# SqTeclado.net
KiCad netlist of a schematic drawn in Altium Designer
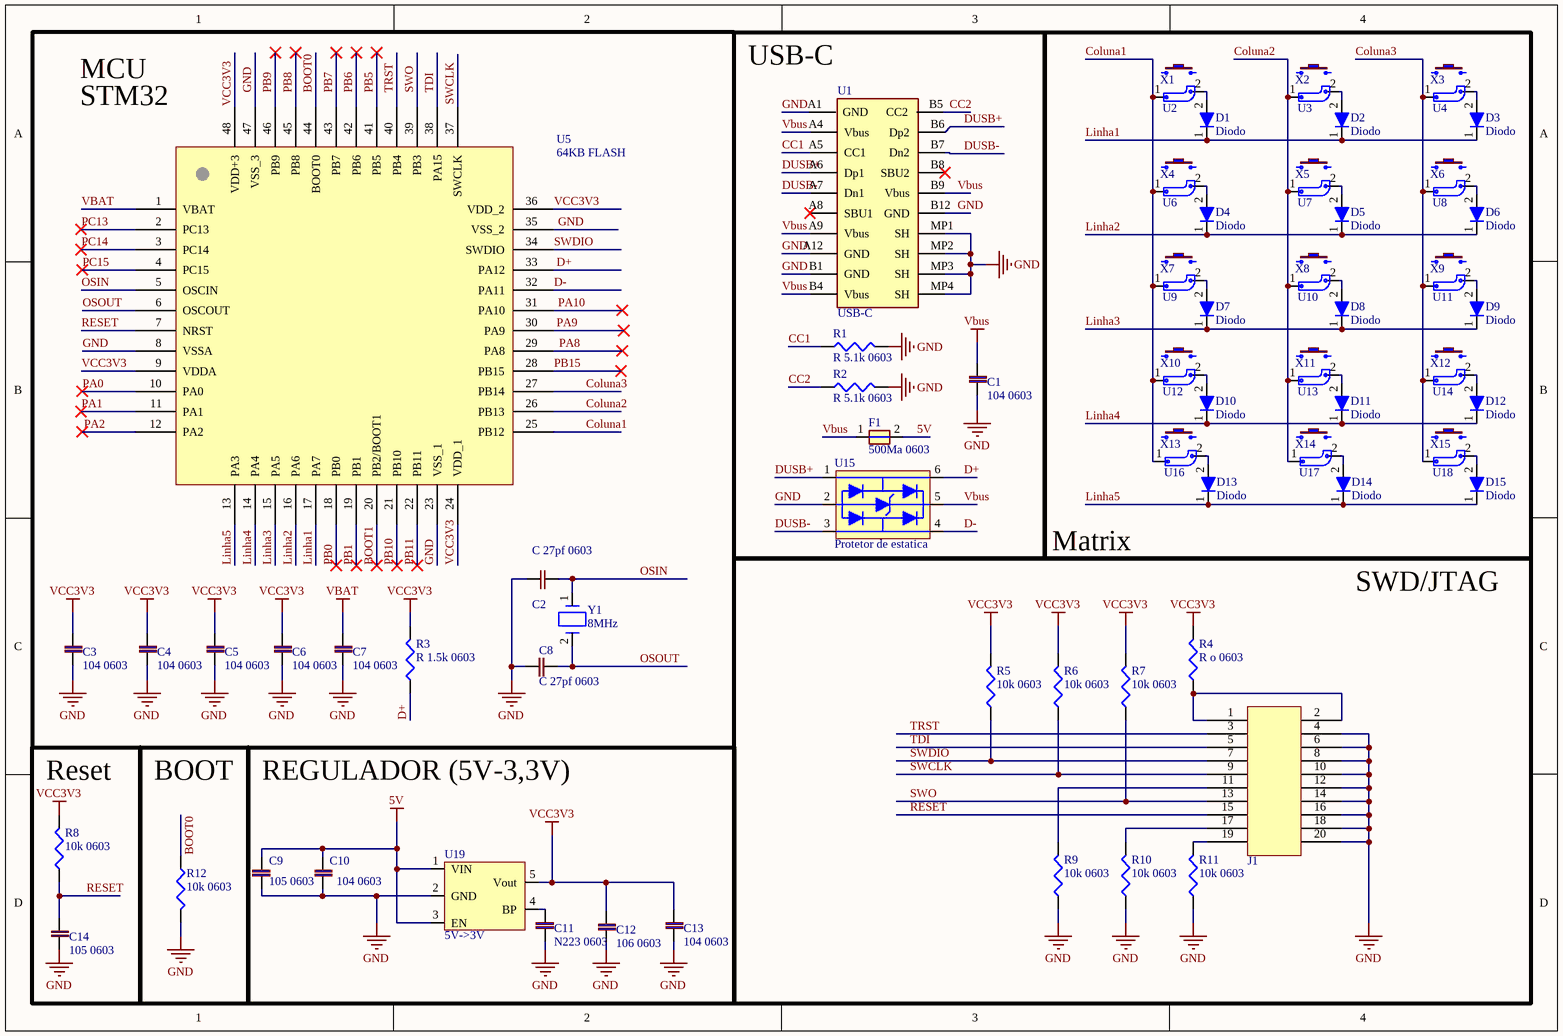
[diagram p0: SqTeclado.SchDoc]

(export (version "E")
  (design (tool "Eeschema 10.0.6"))
  (components
    (comp (ref "C1")
      (value "104 0603")
      (footprint "Cap 104 0603")
      (description "16V 100nF X7R ±10% 0603 Multilayer Ceramic Capacitors MLCC - SMD/SMT ROHS")
      (fields
        (field (name "MANUFACTURER") "Yageo Group")
        (field (name "MANUFACTURER PART NUMBER") "CC0603KRX7R7BB104")
      )
      (libsource (lib "Esqlib") (part "CC0603KRX7R7BB104"))
    )
    (comp (ref "C2")
      (value "C 27pf 0603")
      (footprint "c 27pf 0603")
      (description "0603 27 pF 50 V ±1 % Tolerance NP0 SMT Multilayer Ceramic Capacitor")
      (fields
        (field (name "MANUFACTURER") "Yageo Group")
        (field (name "MANUFACTURER PART NUMBER") "CC0603FRNPO9BN270")
      )
      (libsource (lib "Esqlib") (part "CC0603FRNPO9BN270"))
    )
    (comp (ref "C3")
      (value "104 0603")
      (footprint "Cap 104 0603")
      (description "16V 100nF X7R ±10% 0603 Multilayer Ceramic Capacitors MLCC - SMD/SMT ROHS")
      (fields
        (field (name "MANUFACTURER") "Yageo Group")
        (field (name "MANUFACTURER PART NUMBER") "CC0603KRX7R7BB104")
      )
      (libsource (lib "Esqlib") (part "CC0603KRX7R7BB104"))
    )
    (comp (ref "C4")
      (value "104 0603")
      (footprint "Cap 104 0603")
      (description "16V 100nF X7R ±10% 0603 Multilayer Ceramic Capacitors MLCC - SMD/SMT ROHS")
      (fields
        (field (name "MANUFACTURER") "Yageo Group")
        (field (name "MANUFACTURER PART NUMBER") "CC0603KRX7R7BB104")
      )
      (libsource (lib "Esqlib") (part "CC0603KRX7R7BB104"))
    )
    (comp (ref "C5")
      (value "104 0603")
      (footprint "Cap 104 0603")
      (description "16V 100nF X7R ±10% 0603 Multilayer Ceramic Capacitors MLCC - SMD/SMT ROHS")
      (fields
        (field (name "MANUFACTURER") "Yageo Group")
        (field (name "MANUFACTURER PART NUMBER") "CC0603KRX7R7BB104")
      )
      (libsource (lib "Esqlib") (part "CC0603KRX7R7BB104"))
    )
    (comp (ref "C6")
      (value "104 0603")
      (footprint "Cap 104 0603")
      (description "16V 100nF X7R ±10% 0603 Multilayer Ceramic Capacitors MLCC - SMD/SMT ROHS")
      (fields
        (field (name "MANUFACTURER") "Yageo Group")
        (field (name "MANUFACTURER PART NUMBER") "CC0603KRX7R7BB104")
      )
      (libsource (lib "Esqlib") (part "CC0603KRX7R7BB104"))
    )
    (comp (ref "C7")
      (value "104 0603")
      (footprint "Cap 104 0603")
      (description "16V 100nF X7R ±10% 0603 Multilayer Ceramic Capacitors MLCC - SMD/SMT ROHS")
      (fields
        (field (name "MANUFACTURER") "Yageo Group")
        (field (name "MANUFACTURER PART NUMBER") "CC0603KRX7R7BB104")
      )
      (libsource (lib "Esqlib") (part "CC0603KRX7R7BB104"))
    )
    (comp (ref "C8")
      (value "C 27pf 0603")
      (footprint "c 27pf 0603")
      (description "0603 27 pF 50 V ±1 % Tolerance NP0 SMT Multilayer Ceramic Capacitor")
      (fields
        (field (name "MANUFACTURER") "Yageo Group")
        (field (name "MANUFACTURER PART NUMBER") "CC0603FRNPO9BN270")
      )
      (libsource (lib "Esqlib") (part "CC0603FRNPO9BN270"))
    )
    (comp (ref "C9")
      (value "105 0603")
      (footprint "cap 105 0603")
      (description "10V 1uF X7R ±10% 0603 Multilayer Ceramic Capacitors MLCC - SMD/SMT ROHS")
      (fields
        (field (name "MANUFACTURER") "Samsung Electro-Mechanics")
        (field (name "MANUFACTURER PART NUMBER") "CL10B105KP8NNNC")
      )
      (libsource (lib "") (part "CL10B105KP8NNNC_1"))
    )
    (comp (ref "C10")
      (value "104 0603")
      (footprint "Cap 104 0603")
      (description "16V 100nF X7R ±10% 0603 Multilayer Ceramic Capacitors MLCC - SMD/SMT ROHS")
      (fields
        (field (name "MANUFACTURER") "Yageo Group")
        (field (name "MANUFACTURER PART NUMBER") "CC0603KRX7R7BB104")
      )
      (libsource (lib "Esqlib") (part "CC0603KRX7R7BB104"))
    )
    (comp (ref "C11")
      (value "N223 0603")
      (footprint "cap 223 0603")
      (fields
        (field (name "MANUFACTURER") "Samsung Electro-Mechanics")
        (field (name "MANUFACTURER PART NUMBER") "CL10B223KB8WPNC")
        (field (name "TOLERANCE") "10%")
      )
      (libsource (lib "Esqlib") (part "CL10B223KB8WPNC"))
    )
    (comp (ref "C12")
      (value "106 0603")
      (footprint "cap 106 0603")
      (description "Multilayer Ceramic Capacitors (High dielectric type), 10V, 10 uF, ± 20 %, 0603, X5R, RoHS")
      (fields
        (field (name "MANUFACTURER") "Taiyo Yuden")
        (field (name "MANUFACTURER PART NUMBER") "LMK107BBJ106MALT")
      )
      (libsource (lib "Esqlib") (part "LMK107BBJ106MALT"))
    )
    (comp (ref "C13")
      (value "104 0603")
      (footprint "Cap 104 0603")
      (description "16V 100nF X7R ±10% 0603 Multilayer Ceramic Capacitors MLCC - SMD/SMT ROHS")
      (fields
        (field (name "MANUFACTURER") "Yageo Group")
        (field (name "MANUFACTURER PART NUMBER") "CC0603KRX7R7BB104")
      )
      (libsource (lib "Esqlib") (part "CC0603KRX7R7BB104"))
    )
    (comp (ref "C14")
      (value "105 0603")
      (footprint "cap 105 0603")
      (description "10V 1uF X7R ±10% 0603 Multilayer Ceramic Capacitors MLCC - SMD/SMT ROHS")
      (fields
        (field (name "MANUFACTURER") "Samsung Electro-Mechanics")
        (field (name "MANUFACTURER PART NUMBER") "CL10B105KP8NNNC")
      )
      (libsource (lib "Esqlib") (part "CL10B105KP8NNNC"))
    )
    (comp (ref "D1")
      (value "Diodo")
      (footprint "Diodo C")
      (description "Rectifier Diode Schottky 40V 0.03A 2-Pin SOD-323 T/R / DIODE SCHOTTKY 30V 30MA SOD323")
      (fields (field (name "MANUFACTURER") "onsemi") (field (name "MANUFACTURER PART NUMBER") "RB751V40T1G"))
      (libsource (lib "Esqlib") (part "RB751V40T1G"))
    )
    (comp (ref "D2")
      (value "Diodo")
      (footprint "Diodo C")
      (description "Rectifier Diode Schottky 40V 0.03A 2-Pin SOD-323 T/R / DIODE SCHOTTKY 30V 30MA SOD323")
      (fields (field (name "MANUFACTURER") "onsemi") (field (name "MANUFACTURER PART NUMBER") "RB751V40T1G"))
      (libsource (lib "Esqlib") (part "RB751V40T1G"))
    )
    (comp (ref "D3")
      (value "Diodo")
      (footprint "Diodo C")
      (description "Rectifier Diode Schottky 40V 0.03A 2-Pin SOD-323 T/R / DIODE SCHOTTKY 30V 30MA SOD323")
      (fields (field (name "MANUFACTURER") "onsemi") (field (name "MANUFACTURER PART NUMBER") "RB751V40T1G"))
      (libsource (lib "Esqlib") (part "RB751V40T1G"))
    )
    (comp (ref "D4")
      (value "Diodo")
      (footprint "Diodo C")
      (description "Rectifier Diode Schottky 40V 0.03A 2-Pin SOD-323 T/R / DIODE SCHOTTKY 30V 30MA SOD323")
      (fields (field (name "MANUFACTURER") "onsemi") (field (name "MANUFACTURER PART NUMBER") "RB751V40T1G"))
      (libsource (lib "Esqlib") (part "RB751V40T1G"))
    )
    (comp (ref "D5")
      (value "Diodo")
      (footprint "Diodo C")
      (description "Rectifier Diode Schottky 40V 0.03A 2-Pin SOD-323 T/R / DIODE SCHOTTKY 30V 30MA SOD323")
      (fields (field (name "MANUFACTURER") "onsemi") (field (name "MANUFACTURER PART NUMBER") "RB751V40T1G"))
      (libsource (lib "Esqlib") (part "RB751V40T1G"))
    )
    (comp (ref "D6")
      (value "Diodo")
      (footprint "Diodo C")
      (description "Rectifier Diode Schottky 40V 0.03A 2-Pin SOD-323 T/R / DIODE SCHOTTKY 30V 30MA SOD323")
      (fields (field (name "MANUFACTURER") "onsemi") (field (name "MANUFACTURER PART NUMBER") "RB751V40T1G"))
      (libsource (lib "Esqlib") (part "RB751V40T1G"))
    )
    (comp (ref "D7")
      (value "Diodo")
      (footprint "Diodo C")
      (description "Rectifier Diode Schottky 40V 0.03A 2-Pin SOD-323 T/R / DIODE SCHOTTKY 30V 30MA SOD323")
      (fields (field (name "MANUFACTURER") "onsemi") (field (name "MANUFACTURER PART NUMBER") "RB751V40T1G"))
      (libsource (lib "Esqlib") (part "RB751V40T1G"))
    )
    (comp (ref "D8")
      (value "Diodo")
      (footprint "Diodo C")
      (description "Rectifier Diode Schottky 40V 0.03A 2-Pin SOD-323 T/R / DIODE SCHOTTKY 30V 30MA SOD323")
      (fields (field (name "MANUFACTURER") "onsemi") (field (name "MANUFACTURER PART NUMBER") "RB751V40T1G"))
      (libsource (lib "Esqlib") (part "RB751V40T1G"))
    )
    (comp (ref "D9")
      (value "Diodo")
      (footprint "Diodo C")
      (description "Rectifier Diode Schottky 40V 0.03A 2-Pin SOD-323 T/R / DIODE SCHOTTKY 30V 30MA SOD323")
      (fields (field (name "MANUFACTURER") "onsemi") (field (name "MANUFACTURER PART NUMBER") "RB751V40T1G"))
      (libsource (lib "Esqlib") (part "RB751V40T1G"))
    )
    (comp (ref "D10")
      (value "Diodo")
      (footprint "Diodo C")
      (description "Rectifier Diode Schottky 40V 0.03A 2-Pin SOD-323 T/R / DIODE SCHOTTKY 30V 30MA SOD323")
      (fields (field (name "MANUFACTURER") "onsemi") (field (name "MANUFACTURER PART NUMBER") "RB751V40T1G"))
      (libsource (lib "Esqlib") (part "RB751V40T1G"))
    )
    (comp (ref "D11")
      (value "Diodo")
      (footprint "Diodo C")
      (description "Rectifier Diode Schottky 40V 0.03A 2-Pin SOD-323 T/R / DIODE SCHOTTKY 30V 30MA SOD323")
      (fields (field (name "MANUFACTURER") "onsemi") (field (name "MANUFACTURER PART NUMBER") "RB751V40T1G"))
      (libsource (lib "Esqlib") (part "RB751V40T1G"))
    )
    (comp (ref "D12")
      (value "Diodo")
      (footprint "Diodo C")
      (description "Rectifier Diode Schottky 40V 0.03A 2-Pin SOD-323 T/R / DIODE SCHOTTKY 30V 30MA SOD323")
      (fields (field (name "MANUFACTURER") "onsemi") (field (name "MANUFACTURER PART NUMBER") "RB751V40T1G"))
      (libsource (lib "Esqlib") (part "RB751V40T1G"))
    )
    (comp (ref "D13")
      (value "Diodo")
      (footprint "Diodo C")
      (description "Rectifier Diode Schottky 40V 0.03A 2-Pin SOD-323 T/R / DIODE SCHOTTKY 30V 30MA SOD323")
      (fields (field (name "MANUFACTURER") "onsemi") (field (name "MANUFACTURER PART NUMBER") "RB751V40T1G"))
      (libsource (lib "Esqlib") (part "RB751V40T1G"))
    )
    (comp (ref "D14")
      (value "Diodo")
      (footprint "Diodo C")
      (description "Rectifier Diode Schottky 40V 0.03A 2-Pin SOD-323 T/R / DIODE SCHOTTKY 30V 30MA SOD323")
      (fields (field (name "MANUFACTURER") "onsemi") (field (name "MANUFACTURER PART NUMBER") "RB751V40T1G"))
      (libsource (lib "Esqlib") (part "RB751V40T1G"))
    )
    (comp (ref "D15")
      (value "Diodo")
      (footprint "Diodo C")
      (description "Rectifier Diode Schottky 40V 0.03A 2-Pin SOD-323 T/R / DIODE SCHOTTKY 30V 30MA SOD323")
      (fields (field (name "MANUFACTURER") "onsemi") (field (name "MANUFACTURER PART NUMBER") "RB751V40T1G"))
      (libsource (lib "Esqlib") (part "RB751V40T1G"))
    )
    (comp (ref "F1")
      (value "500Ma 0603")
      (footprint "F 500ma 0603")
      (description "Fuse Chip Fast Acting 0.5A 32V SMD Solder Pad 0603 1.6 X 0.8 X 0.54mm T/R UL/cUL")
      (fields
        (field (name "MANUFACTURER") "Panasonic")
        (field (name "MANUFACTURER PART NUMBER") "ERB-RE0R50V")
      )
      (libsource (lib "Esqlib") (part "ERB-RE0R50V"))
    )
    (comp (ref "J1")
      (value "70247-2051")
      (footprint "Conector 20 pinos angulado p/ programação")
      (description "Conn Shrouded Header (4 Sides) HDR 20 POS 2.54mm Solder RA Side Entry Thru-HoleC-Grid Tray")
      (fields (field (name "MANUFACTURER") "Molex"))
      (libsource (lib "Esqlib") (part "70247-2051"))
    )
    (comp (ref "R1")
      (value "R 5.1k 0603")
      (footprint "R 5.1k 0603")
      (description "Res Thick Film 0603 5.1K Ohm 1% 0.1W(1/10W) ±100ppm/C Pad SMD T/R")
      (fields
        (field (name "MANUFACTURER") "Yageo Group")
        (field (name "MANUFACTURER PART NUMBER") "RC0603FR-075K1L")
      )
      (libsource (lib "Esqlib") (part "RC0603FR-075K1L"))
    )
    (comp (ref "R2")
      (value "R 5.1k 0603")
      (footprint "R 5.1k 0603")
      (description "Res Thick Film 0603 5.1K Ohm 1% 0.1W(1/10W) ±100ppm/C Pad SMD T/R")
      (fields
        (field (name "MANUFACTURER") "Yageo Group")
        (field (name "MANUFACTURER PART NUMBER") "RC0603FR-075K1L")
      )
      (libsource (lib "Esqlib") (part "RC0603FR-075K1L"))
    )
    (comp (ref "R3")
      (value "R 1.5k 0603")
      (footprint "R 1.5k 0603")
      (description "100Mw Thick Film Resistors 100Ppm/ 5% 1.5K 0603 Chip Resistor Surface Mount Rohs")
      (fields
        (field (name "MANUFACTURER") "Yageo Group")
        (field (name "MANUFACTURER PART NUMBER") "RC0603JR-071K5L")
      )
      (libsource (lib "Esqlib") (part "RC0603JR-071K5L"))
    )
    (comp (ref "R4")
      (value "R o 0603")
      (footprint "R 0 0603")
      (description "GENERAL PURPOSE CHIP RESISTOR Metal Glaze/thick Film, 0.1W, 0ohm, Surface Mount, 0603")
      (fields
        (field (name "MANUFACTURER") "Yageo Group")
        (field (name "MANUFACTURER PART NUMBER") "RC0603JR-070RL")
      )
      (libsource (lib "Esqlib") (part "RC0603JR-070RL"))
    )
    (comp (ref "R5")
      (value "10k 0603")
      (footprint "Resistor 10k 0603")
      (description "100mW Thick Film Resistors ±1% ±100ppm/℃ 10kΩ 0603 Chip Resistor - Surface Mount ROHS")
      (fields
        (field (name "MANUFACTURER") "Vishay")
        (field (name "MANUFACTURER PART NUMBER") "CRCW060310K0FKEA")
      )
      (libsource (lib "Esqlib") (part "CRCW060310K0FKEA"))
    )
    (comp (ref "R6")
      (value "10k 0603")
      (footprint "Resistor 10k 0603")
      (description "100mW Thick Film Resistors ±1% ±100ppm/℃ 10kΩ 0603 Chip Resistor - Surface Mount ROHS")
      (fields
        (field (name "MANUFACTURER") "Vishay")
        (field (name "MANUFACTURER PART NUMBER") "CRCW060310K0FKEA")
      )
      (libsource (lib "Esqlib") (part "CRCW060310K0FKEA"))
    )
    (comp (ref "R7")
      (value "10k 0603")
      (footprint "Resistor 10k 0603")
      (description "100mW Thick Film Resistors ±1% ±100ppm/℃ 10kΩ 0603 Chip Resistor - Surface Mount ROHS")
      (fields
        (field (name "MANUFACTURER") "Vishay")
        (field (name "MANUFACTURER PART NUMBER") "CRCW060310K0FKEA")
      )
      (libsource (lib "Esqlib") (part "CRCW060310K0FKEA"))
    )
    (comp (ref "R8")
      (value "10k 0603")
      (footprint "Resistor 10k 0603")
      (description "100mW Thick Film Resistors ±1% ±100ppm/℃ 10kΩ 0603 Chip Resistor - Surface Mount ROHS")
      (fields
        (field (name "MANUFACTURER") "Vishay")
        (field (name "MANUFACTURER PART NUMBER") "CRCW060310K0FKEA")
      )
      (libsource (lib "Esqlib") (part "CRCW060310K0FKEA"))
    )
    (comp (ref "R9")
      (value "10k 0603")
      (footprint "Resistor 10k 0603")
      (description "100mW Thick Film Resistors ±1% ±100ppm/℃ 10kΩ 0603 Chip Resistor - Surface Mount ROHS")
      (fields
        (field (name "MANUFACTURER") "Vishay")
        (field (name "MANUFACTURER PART NUMBER") "CRCW060310K0FKEA")
      )
      (libsource (lib "Esqlib") (part "CRCW060310K0FKEA"))
    )
    (comp (ref "R10")
      (value "10k 0603")
      (footprint "Resistor 10k 0603")
      (description "100mW Thick Film Resistors ±1% ±100ppm/℃ 10kΩ 0603 Chip Resistor - Surface Mount ROHS")
      (fields
        (field (name "MANUFACTURER") "Vishay")
        (field (name "MANUFACTURER PART NUMBER") "CRCW060310K0FKEA")
      )
      (libsource (lib "Esqlib") (part "CRCW060310K0FKEA"))
    )
    (comp (ref "R11")
      (value "10k 0603")
      (footprint "Resistor 10k 0603")
      (description "100mW Thick Film Resistors ±1% ±100ppm/℃ 10kΩ 0603 Chip Resistor - Surface Mount ROHS")
      (fields
        (field (name "MANUFACTURER") "Vishay")
        (field (name "MANUFACTURER PART NUMBER") "CRCW060310K0FKEA")
      )
      (libsource (lib "Esqlib") (part "CRCW060310K0FKEA"))
    )
    (comp (ref "R12")
      (value "10k 0603")
      (footprint "Resistor 10k 0603")
      (description "100mW Thick Film Resistors ±1% ±100ppm/℃ 10kΩ 0603 Chip Resistor - Surface Mount ROHS")
      (fields
        (field (name "MANUFACTURER") "Vishay")
        (field (name "MANUFACTURER PART NUMBER") "CRCW060310K0FKEA")
      )
      (libsource (lib "Esqlib") (part "CRCW060310K0FKEA"))
    )
    (comp (ref "U1")
      (value "USB-C")
      (footprint "USB-C")
      (description "USB Connector, 16 Contact(s), Male, Right Angle, Surface Mount Terminal, Locking, Receptacle")
      (fields
        (field (name "MANUFACTURER") "Global Connector Technology")
        (field (name "MANUFACTURER PART NUMBER") "USB4110-GF-A")
      )
      (libsource (lib "Esqlib") (part "USB4110-GF-A"))
    )
    (comp (ref "U2")
      (value "suporte hot-swap")
      (footprint "Suporte Hot-Swap")
      (description "Kailh Switch Sockets For Mx-Compatible Mechanical Keys - 20 Pack ¦Adafruit 4958")
      (fields
        (field (name "MANUFACTURER") "Adafruit Industries")
        (field (name "MANUFACTURER PART NUMBER") "4958")
      )
      (libsource (lib "Esqlib") (part "4958"))
    )
    (comp (ref "U3")
      (value "suporte hot-swap")
      (footprint "Suporte Hot-Swap")
      (description "Kailh Switch Sockets For Mx-Compatible Mechanical Keys - 20 Pack ¦Adafruit 4958")
      (fields
        (field (name "MANUFACTURER") "Adafruit Industries")
        (field (name "MANUFACTURER PART NUMBER") "4958")
      )
      (libsource (lib "Esqlib") (part "4958"))
    )
    (comp (ref "U4")
      (value "suporte hot-swap")
      (footprint "Suporte Hot-Swap")
      (description "Kailh Switch Sockets For Mx-Compatible Mechanical Keys - 20 Pack ¦Adafruit 4958")
      (fields
        (field (name "MANUFACTURER") "Adafruit Industries")
        (field (name "MANUFACTURER PART NUMBER") "4958")
      )
      (libsource (lib "Esqlib") (part "4958"))
    )
    (comp (ref "U5")
      (value "64KB FLASH")
      (footprint "STM32F103C8T6")
      (description "MCU 32-bit STM32F1 ARM Cortex M3 RISC 64KB Flash 2.5V/3.3V 48-Pin LQFP Tray")
      (fields
        (field (name "MANUFACTURER") "STMicroelectronics")
        (field (name "MANUFACTURER PART NUMBER") "STM32F103C8T6")
      )
      (libsource (lib "Esqlib") (part "STM32F103C8T6"))
    )
    (comp (ref "U6")
      (value "suporte hot-swap")
      (footprint "Suporte Hot-Swap")
      (description "Kailh Switch Sockets For Mx-Compatible Mechanical Keys - 20 Pack ¦Adafruit 4958")
      (fields
        (field (name "MANUFACTURER") "Adafruit Industries")
        (field (name "MANUFACTURER PART NUMBER") "4958")
      )
      (libsource (lib "Esqlib") (part "4958"))
    )
    (comp (ref "U7")
      (value "suporte hot-swap")
      (footprint "Suporte Hot-Swap")
      (description "Kailh Switch Sockets For Mx-Compatible Mechanical Keys - 20 Pack ¦Adafruit 4958")
      (fields
        (field (name "MANUFACTURER") "Adafruit Industries")
        (field (name "MANUFACTURER PART NUMBER") "4958")
      )
      (libsource (lib "Esqlib") (part "4958"))
    )
    (comp (ref "U8")
      (value "suporte hot-swap")
      (footprint "Suporte Hot-Swap")
      (description "Kailh Switch Sockets For Mx-Compatible Mechanical Keys - 20 Pack ¦Adafruit 4958")
      (fields
        (field (name "MANUFACTURER") "Adafruit Industries")
        (field (name "MANUFACTURER PART NUMBER") "4958")
      )
      (libsource (lib "Esqlib") (part "4958"))
    )
    (comp (ref "U9")
      (value "suporte hot-swap")
      (footprint "Suporte Hot-Swap")
      (description "Kailh Switch Sockets For Mx-Compatible Mechanical Keys - 20 Pack ¦Adafruit 4958")
      (fields
        (field (name "MANUFACTURER") "Adafruit Industries")
        (field (name "MANUFACTURER PART NUMBER") "4958")
      )
      (libsource (lib "Esqlib") (part "4958"))
    )
    (comp (ref "U10")
      (value "suporte hot-swap")
      (footprint "Suporte Hot-Swap")
      (description "Kailh Switch Sockets For Mx-Compatible Mechanical Keys - 20 Pack ¦Adafruit 4958")
      (fields
        (field (name "MANUFACTURER") "Adafruit Industries")
        (field (name "MANUFACTURER PART NUMBER") "4958")
      )
      (libsource (lib "Esqlib") (part "4958"))
    )
    (comp (ref "U11")
      (value "suporte hot-swap")
      (footprint "Suporte Hot-Swap")
      (description "Kailh Switch Sockets For Mx-Compatible Mechanical Keys - 20 Pack ¦Adafruit 4958")
      (fields
        (field (name "MANUFACTURER") "Adafruit Industries")
        (field (name "MANUFACTURER PART NUMBER") "4958")
      )
      (libsource (lib "Esqlib") (part "4958"))
    )
    (comp (ref "U12")
      (value "suporte hot-swap")
      (footprint "Suporte Hot-Swap")
      (description "Kailh Switch Sockets For Mx-Compatible Mechanical Keys - 20 Pack ¦Adafruit 4958")
      (fields
        (field (name "MANUFACTURER") "Adafruit Industries")
        (field (name "MANUFACTURER PART NUMBER") "4958")
      )
      (libsource (lib "Esqlib") (part "4958"))
    )
    (comp (ref "U13")
      (value "suporte hot-swap")
      (footprint "Suporte Hot-Swap")
      (description "Kailh Switch Sockets For Mx-Compatible Mechanical Keys - 20 Pack ¦Adafruit 4958")
      (fields
        (field (name "MANUFACTURER") "Adafruit Industries")
        (field (name "MANUFACTURER PART NUMBER") "4958")
      )
      (libsource (lib "Esqlib") (part "4958"))
    )
    (comp (ref "U14")
      (value "suporte hot-swap")
      (footprint "Suporte Hot-Swap")
      (description "Kailh Switch Sockets For Mx-Compatible Mechanical Keys - 20 Pack ¦Adafruit 4958")
      (fields
        (field (name "MANUFACTURER") "Adafruit Industries")
        (field (name "MANUFACTURER PART NUMBER") "4958")
      )
      (libsource (lib "Esqlib") (part "4958"))
    )
    (comp (ref "U15")
      (value "Protetor de estatica")
      (footprint "Potege estatica")
      (description "USBLC6 Series 2 Line 6 V Uni / Bi-Directional ESD Protection - SOT-23-6")
      (fields
        (field (name "MANUFACTURER") "STMicroelectronics")
        (field (name "MANUFACTURER PART NUMBER") "USBLC6-2SC6")
      )
      (libsource (lib "Esqlib") (part "USBLC6-2SC6"))
    )
    (comp (ref "U16")
      (value "suporte hot-swap")
      (footprint "Suporte Hot-Swap")
      (description "Kailh Switch Sockets For Mx-Compatible Mechanical Keys - 20 Pack ¦Adafruit 4958")
      (fields
        (field (name "MANUFACTURER") "Adafruit Industries")
        (field (name "MANUFACTURER PART NUMBER") "4958")
      )
      (libsource (lib "Esqlib") (part "4958"))
    )
    (comp (ref "U17")
      (value "suporte hot-swap")
      (footprint "Suporte Hot-Swap")
      (description "Kailh Switch Sockets For Mx-Compatible Mechanical Keys - 20 Pack ¦Adafruit 4958")
      (fields
        (field (name "MANUFACTURER") "Adafruit Industries")
        (field (name "MANUFACTURER PART NUMBER") "4958")
      )
      (libsource (lib "Esqlib") (part "4958"))
    )
    (comp (ref "U18")
      (value "suporte hot-swap")
      (footprint "Suporte Hot-Swap")
      (description "Kailh Switch Sockets For Mx-Compatible Mechanical Keys - 20 Pack ¦Adafruit 4958")
      (fields
        (field (name "MANUFACTURER") "Adafruit Industries")
        (field (name "MANUFACTURER PART NUMBER") "4958")
      )
      (libsource (lib "Esqlib") (part "4958"))
    )
    (comp (ref "U19")
      (value "5V->3V")
      (footprint "Regulador 5v->3v")
      (description "RT9193 Series 300 mA 3.3 V Ultra-Low Noise Ultra-Fast CMOS LDO Regulator-SC-70-5")
      (fields (field (name "MANUFACTURER") "Richtek") (field (name "MANUFACTURER PART NUMBER") "RT9193-33GB"))
      (libsource (lib "Esqlib") (part "RT9193-33GB"))
    )
    (comp (ref "X1")
      (value "switch")
      (footprint "tecla")
      (description "Switch, Key, Spst-no, Keyboard, Low Profile, 10MA, 12VDC, Soft Tactile, Fp Mnt, Std Force")
      (fields (field (name "MANUFACTURER") "Cherry") (field (name "MANUFACTURER PART NUMBER") "MX1A-C1NN"))
      (libsource (lib "Esqlib") (part "MX1A-C1NN"))
    )
    (comp (ref "X2")
      (value "switch")
      (footprint "tecla")
      (description "Switch, Key, Spst-no, Keyboard, Low Profile, 10MA, 12VDC, Soft Tactile, Fp Mnt, Std Force")
      (fields (field (name "MANUFACTURER") "Cherry") (field (name "MANUFACTURER PART NUMBER") "MX1A-C1NN"))
      (libsource (lib "Esqlib") (part "MX1A-C1NN"))
    )
    (comp (ref "X3")
      (value "switch")
      (footprint "tecla")
      (description "Switch, Key, Spst-no, Keyboard, Low Profile, 10MA, 12VDC, Soft Tactile, Fp Mnt, Std Force")
      (fields (field (name "MANUFACTURER") "Cherry") (field (name "MANUFACTURER PART NUMBER") "MX1A-C1NN"))
      (libsource (lib "Esqlib") (part "MX1A-C1NN"))
    )
    (comp (ref "X4")
      (value "switch")
      (footprint "tecla")
      (description "Switch, Key, Spst-no, Keyboard, Low Profile, 10MA, 12VDC, Soft Tactile, Fp Mnt, Std Force")
      (fields (field (name "MANUFACTURER") "Cherry") (field (name "MANUFACTURER PART NUMBER") "MX1A-C1NN"))
      (libsource (lib "Esqlib") (part "MX1A-C1NN"))
    )
    (comp (ref "X5")
      (value "switch")
      (footprint "tecla")
      (description "Switch, Key, Spst-no, Keyboard, Low Profile, 10MA, 12VDC, Soft Tactile, Fp Mnt, Std Force")
      (fields (field (name "MANUFACTURER") "Cherry") (field (name "MANUFACTURER PART NUMBER") "MX1A-C1NN"))
      (libsource (lib "Esqlib") (part "MX1A-C1NN"))
    )
    (comp (ref "X6")
      (value "switch")
      (footprint "tecla")
      (description "Switch, Key, Spst-no, Keyboard, Low Profile, 10MA, 12VDC, Soft Tactile, Fp Mnt, Std Force")
      (fields (field (name "MANUFACTURER") "Cherry") (field (name "MANUFACTURER PART NUMBER") "MX1A-C1NN"))
      (libsource (lib "Esqlib") (part "MX1A-C1NN"))
    )
    (comp (ref "X7")
      (value "switch")
      (footprint "tecla")
      (description "Switch, Key, Spst-no, Keyboard, Low Profile, 10MA, 12VDC, Soft Tactile, Fp Mnt, Std Force")
      (fields (field (name "MANUFACTURER") "Cherry") (field (name "MANUFACTURER PART NUMBER") "MX1A-C1NN"))
      (libsource (lib "Esqlib") (part "MX1A-C1NN"))
    )
    (comp (ref "X8")
      (value "switch")
      (footprint "tecla")
      (description "Switch, Key, Spst-no, Keyboard, Low Profile, 10MA, 12VDC, Soft Tactile, Fp Mnt, Std Force")
      (fields (field (name "MANUFACTURER") "Cherry") (field (name "MANUFACTURER PART NUMBER") "MX1A-C1NN"))
      (libsource (lib "Esqlib") (part "MX1A-C1NN"))
    )
    (comp (ref "X9")
      (value "switch")
      (footprint "tecla")
      (description "Switch, Key, Spst-no, Keyboard, Low Profile, 10MA, 12VDC, Soft Tactile, Fp Mnt, Std Force")
      (fields (field (name "MANUFACTURER") "Cherry") (field (name "MANUFACTURER PART NUMBER") "MX1A-C1NN"))
      (libsource (lib "Esqlib") (part "MX1A-C1NN"))
    )
    (comp (ref "X10")
      (value "switch")
      (footprint "tecla")
      (description "Switch, Key, Spst-no, Keyboard, Low Profile, 10MA, 12VDC, Soft Tactile, Fp Mnt, Std Force")
      (fields (field (name "MANUFACTURER") "Cherry") (field (name "MANUFACTURER PART NUMBER") "MX1A-C1NN"))
      (libsource (lib "Esqlib") (part "MX1A-C1NN"))
    )
    (comp (ref "X11")
      (value "switch")
      (footprint "tecla")
      (description "Switch, Key, Spst-no, Keyboard, Low Profile, 10MA, 12VDC, Soft Tactile, Fp Mnt, Std Force")
      (fields (field (name "MANUFACTURER") "Cherry") (field (name "MANUFACTURER PART NUMBER") "MX1A-C1NN"))
      (libsource (lib "Esqlib") (part "MX1A-C1NN"))
    )
    (comp (ref "X12")
      (value "switch")
      (footprint "tecla")
      (description "Switch, Key, Spst-no, Keyboard, Low Profile, 10MA, 12VDC, Soft Tactile, Fp Mnt, Std Force")
      (fields (field (name "MANUFACTURER") "Cherry") (field (name "MANUFACTURER PART NUMBER") "MX1A-C1NN"))
      (libsource (lib "Esqlib") (part "MX1A-C1NN"))
    )
    (comp (ref "X13")
      (value "switch")
      (footprint "tecla")
      (description "Switch, Key, Spst-no, Keyboard, Low Profile, 10MA, 12VDC, Soft Tactile, Fp Mnt, Std Force")
      (fields (field (name "MANUFACTURER") "Cherry") (field (name "MANUFACTURER PART NUMBER") "MX1A-C1NN"))
      (libsource (lib "Esqlib") (part "MX1A-C1NN"))
    )
    (comp (ref "X14")
      (value "switch")
      (footprint "tecla")
      (description "Switch, Key, Spst-no, Keyboard, Low Profile, 10MA, 12VDC, Soft Tactile, Fp Mnt, Std Force")
      (fields (field (name "MANUFACTURER") "Cherry") (field (name "MANUFACTURER PART NUMBER") "MX1A-C1NN"))
      (libsource (lib "Esqlib") (part "MX1A-C1NN"))
    )
    (comp (ref "X15")
      (value "switch")
      (footprint "tecla")
      (description "Switch, Key, Spst-no, Keyboard, Low Profile, 10MA, 12VDC, Soft Tactile, Fp Mnt, Std Force")
      (fields (field (name "MANUFACTURER") "Cherry") (field (name "MANUFACTURER PART NUMBER") "MX1A-C1NN"))
      (libsource (lib "Esqlib") (part "MX1A-C1NN"))
    )
    (comp (ref "Y1")
      (value "8MHz")
      (footprint "Cristal 8MHz")
      (description "Crystal 8MHz ±30ppm (Tol) ±100ppm (Stability) 20pF FUND 60Ohm 2-Pin SMD T/R")
      (fields
        (field (name "MANUFACTURER") "ECS International")
        (field (name "MANUFACTURER PART NUMBER") "ECS-80-20-5PXDU-TR")
      )
      (libsource (lib "Esqlib") (part "ECS-80-20-5PXDU-TR"))
    )
  )
  (nets
    (net (code "2") (name "/BOOT0") (class "Default")
      (node (ref "R12") (pin "1") (pinfunction "1_1") (pintype "passive"))
      (node (ref "U5") (pin "44") (pinfunction "BOOT0_44") (pintype "passive"))
    )
    (net (code "3") (name "/BOOT1") (class "Default")
      (node (ref "U5") (pin "20") (pinfunction "PB2/BOOT1_20") (pintype "passive+no_connect"))
    )
    (net (code "4") (name "/CC1") (class "Default")
      (node (ref "R1") (pin "1") (pinfunction "1_1") (pintype "passive"))
      (node (ref "U1") (pin "A5") (pinfunction "CC1_A5") (pintype "passive"))
    )
    (net (code "5") (name "/CC2") (class "Default")
      (node (ref "R2") (pin "1") (pinfunction "1_1") (pintype "passive"))
      (node (ref "U1") (pin "B5") (pinfunction "CC2_B5") (pintype "passive"))
    )
    (net (code "6") (name "/Coluna1") (class "Default")
      (node (ref "U12") (pin "1") (pinfunction "1_1") (pintype "passive"))
      (node (ref "U16") (pin "1") (pinfunction "1_1") (pintype "passive"))
      (node (ref "U2") (pin "1") (pinfunction "1_1") (pintype "passive"))
      (node (ref "U5") (pin "25") (pinfunction "PB12_25") (pintype "passive"))
      (node (ref "U6") (pin "1") (pinfunction "1_1") (pintype "passive"))
      (node (ref "U9") (pin "1") (pinfunction "1_1") (pintype "passive"))
    )
    (net (code "7") (name "/Coluna2") (class "Default")
      (node (ref "U10") (pin "1") (pinfunction "1_1") (pintype "passive"))
      (node (ref "U13") (pin "1") (pinfunction "1_1") (pintype "passive"))
      (node (ref "U17") (pin "1") (pinfunction "1_1") (pintype "passive"))
      (node (ref "U3") (pin "1") (pinfunction "1_1") (pintype "passive"))
      (node (ref "U5") (pin "26") (pinfunction "PB13_26") (pintype "passive"))
      (node (ref "U7") (pin "1") (pinfunction "1_1") (pintype "passive"))
    )
    (net (code "8") (name "/Coluna3") (class "Default")
      (node (ref "U11") (pin "1") (pinfunction "1_1") (pintype "passive"))
      (node (ref "U14") (pin "1") (pinfunction "1_1") (pintype "passive"))
      (node (ref "U18") (pin "1") (pinfunction "1_1") (pintype "passive"))
      (node (ref "U4") (pin "1") (pinfunction "1_1") (pintype "passive"))
      (node (ref "U5") (pin "27") (pinfunction "PB14_27") (pintype "passive"))
      (node (ref "U8") (pin "1") (pinfunction "1_1") (pintype "passive"))
    )
    (net (code "9") (name "/D+") (class "Default")
      (node (ref "R3") (pin "1") (pinfunction "1_1") (pintype "passive"))
      (node (ref "U15") (pin "6") (pinfunction "6_6") (pintype "passive"))
      (node (ref "U5") (pin "33") (pinfunction "PA12_33") (pintype "passive"))
    )
    (net (code "10") (name "/D-") (class "Default")
      (node (ref "U15") (pin "4") (pinfunction "4_4") (pintype "passive"))
      (node (ref "U5") (pin "32") (pinfunction "PA11_32") (pintype "passive"))
    )
    (net (code "11") (name "/DUSB+") (class "Default")
      (node (ref "U1") (pin "A6") (pinfunction "Dp1_A6") (pintype "passive"))
      (node (ref "U1") (pin "B6") (pinfunction "Dp2_B6") (pintype "passive"))
      (node (ref "U15") (pin "1") (pinfunction "1_1") (pintype "passive"))
    )
    (net (code "12") (name "/DUSB-") (class "Default")
      (node (ref "U1") (pin "A7") (pinfunction "Dn1_A7") (pintype "passive"))
      (node (ref "U1") (pin "B7") (pinfunction "Dn2_B7") (pintype "passive"))
      (node (ref "U15") (pin "3") (pinfunction "3_3") (pintype "passive"))
    )
    (net (code "13") (name "/Linha1") (class "Default")
      (node (ref "D1") (pin "1") (pinfunction "1_1") (pintype "passive"))
      (node (ref "D2") (pin "1") (pinfunction "1_1") (pintype "passive"))
      (node (ref "D3") (pin "1") (pinfunction "1_1") (pintype "passive"))
      (node (ref "U5") (pin "17") (pinfunction "PA7_17") (pintype "passive"))
    )
    (net (code "14") (name "/Linha2") (class "Default")
      (node (ref "D4") (pin "1") (pinfunction "1_1") (pintype "passive"))
      (node (ref "D5") (pin "1") (pinfunction "1_1") (pintype "passive"))
      (node (ref "D6") (pin "1") (pinfunction "1_1") (pintype "passive"))
      (node (ref "U5") (pin "16") (pinfunction "PA6_16") (pintype "passive"))
    )
    (net (code "15") (name "/Linha3") (class "Default")
      (node (ref "D7") (pin "1") (pinfunction "1_1") (pintype "passive"))
      (node (ref "D8") (pin "1") (pinfunction "1_1") (pintype "passive"))
      (node (ref "D9") (pin "1") (pinfunction "1_1") (pintype "passive"))
      (node (ref "U5") (pin "15") (pinfunction "PA5_15") (pintype "passive"))
    )
    (net (code "16") (name "/Linha4") (class "Default")
      (node (ref "D10") (pin "1") (pinfunction "1_1") (pintype "passive"))
      (node (ref "D11") (pin "1") (pinfunction "1_1") (pintype "passive"))
      (node (ref "D12") (pin "1") (pinfunction "1_1") (pintype "passive"))
      (node (ref "U5") (pin "14") (pinfunction "PA4_14") (pintype "passive"))
    )
    (net (code "17") (name "/Linha5") (class "Default")
      (node (ref "D13") (pin "1") (pinfunction "1_1") (pintype "passive"))
      (node (ref "D14") (pin "1") (pinfunction "1_1") (pintype "passive"))
      (node (ref "D15") (pin "1") (pinfunction "1_1") (pintype "passive"))
      (node (ref "U5") (pin "13") (pinfunction "PA3_13") (pintype "passive"))
    )
    (net (code "18") (name "/OSIN") (class "Default")
      (node (ref "C2") (pin "2") (pinfunction "2_2") (pintype "passive"))
      (node (ref "U5") (pin "5") (pinfunction "OSCIN_5") (pintype "passive"))
      (node (ref "Y1") (pin "1") (pinfunction "1_1") (pintype "passive"))
    )
    (net (code "19") (name "/OSOUT") (class "Default")
      (node (ref "C8") (pin "2") (pinfunction "2_2") (pintype "passive"))
      (node (ref "U5") (pin "6") (pinfunction "OSCOUT_6") (pintype "passive"))
      (node (ref "Y1") (pin "2") (pinfunction "2_2") (pintype "passive"))
    )
    (net (code "20") (name "/PA0") (class "Default")
      (node (ref "U5") (pin "10") (pinfunction "PA0_10") (pintype "passive+no_connect"))
    )
    (net (code "21") (name "/PA1") (class "Default")
      (node (ref "U5") (pin "11") (pinfunction "PA1_11") (pintype "passive+no_connect"))
    )
    (net (code "22") (name "/PA2") (class "Default")
      (node (ref "U5") (pin "12") (pinfunction "PA2_12") (pintype "passive+no_connect"))
    )
    (net (code "23") (name "/PA8") (class "Default")
      (node (ref "U5") (pin "29") (pinfunction "PA8_29") (pintype "passive+no_connect"))
    )
    (net (code "24") (name "/PA9") (class "Default")
      (node (ref "U5") (pin "30") (pinfunction "PA9_30") (pintype "passive+no_connect"))
    )
    (net (code "25") (name "/PA10") (class "Default")
      (node (ref "U5") (pin "31") (pinfunction "PA10_31") (pintype "passive+no_connect"))
    )
    (net (code "26") (name "/PB0") (class "Default")
      (node (ref "U5") (pin "18") (pinfunction "PB0_18") (pintype "passive+no_connect"))
    )
    (net (code "27") (name "/PB1") (class "Default")
      (node (ref "U5") (pin "19") (pinfunction "PB1_19") (pintype "passive+no_connect"))
    )
    (net (code "28") (name "/PB5") (class "Default")
      (node (ref "U5") (pin "41") (pinfunction "PB5_41") (pintype "passive+no_connect"))
    )
    (net (code "29") (name "/PB6") (class "Default")
      (node (ref "U5") (pin "42") (pinfunction "PB6_42") (pintype "passive+no_connect"))
    )
    (net (code "30") (name "/PB7") (class "Default")
      (node (ref "U5") (pin "43") (pinfunction "PB7_43") (pintype "passive+no_connect"))
    )
    (net (code "31") (name "/PB8") (class "Default")
      (node (ref "U5") (pin "45") (pinfunction "PB8_45") (pintype "passive+no_connect"))
    )
    (net (code "32") (name "/PB9") (class "Default")
      (node (ref "U5") (pin "46") (pinfunction "PB9_46") (pintype "passive+no_connect"))
    )
    (net (code "33") (name "/PB10") (class "Default")
      (node (ref "U5") (pin "21") (pinfunction "PB10_21") (pintype "passive+no_connect"))
    )
    (net (code "34") (name "/PB11") (class "Default")
      (node (ref "U5") (pin "22") (pinfunction "PB11_22") (pintype "passive+no_connect"))
    )
    (net (code "35") (name "/PB15") (class "Default")
      (node (ref "U5") (pin "28") (pinfunction "PB15_28") (pintype "passive+no_connect"))
    )
    (net (code "36") (name "/PC13") (class "Default")
      (node (ref "U5") (pin "2") (pinfunction "PC13_2") (pintype "passive+no_connect"))
    )
    (net (code "37") (name "/PC14") (class "Default")
      (node (ref "U5") (pin "3") (pinfunction "PC14_3") (pintype "passive+no_connect"))
    )
    (net (code "38") (name "/PC15") (class "Default")
      (node (ref "U5") (pin "4") (pinfunction "PC15_4") (pintype "passive+no_connect"))
    )
    (net (code "39") (name "/RESET") (class "Default")
      (node (ref "C14") (pin "2") (pinfunction "2_2") (pintype "passive"))
      (node (ref "J1") (pin "15") (pinfunction "15_15") (pintype "passive"))
      (node (ref "R8") (pin "1") (pinfunction "1_1") (pintype "passive"))
      (node (ref "U5") (pin "7") (pinfunction "NRST_7") (pintype "passive"))
    )
    (net (code "40") (name "/SWCLK") (class "Default")
      (node (ref "J1") (pin "9") (pinfunction "9_9") (pintype "passive"))
      (node (ref "R6") (pin "1") (pinfunction "1_1") (pintype "passive"))
      (node (ref "U5") (pin "37") (pinfunction "SWCLK_37") (pintype "passive"))
    )
    (net (code "41") (name "/SWDIO") (class "Default")
      (node (ref "J1") (pin "7") (pinfunction "7_7") (pintype "passive"))
      (node (ref "R5") (pin "1") (pinfunction "1_1") (pintype "passive"))
      (node (ref "U5") (pin "34") (pinfunction "SWDIO_34") (pintype "passive"))
    )
    (net (code "42") (name "/SWO") (class "Default")
      (node (ref "J1") (pin "13") (pinfunction "13_13") (pintype "passive"))
      (node (ref "R7") (pin "1") (pinfunction "1_1") (pintype "passive"))
      (node (ref "U5") (pin "39") (pinfunction "PB3_39") (pintype "passive"))
    )
    (net (code "43") (name "/TDI") (class "Default")
      (node (ref "J1") (pin "5") (pinfunction "5_5") (pintype "passive"))
      (node (ref "U5") (pin "38") (pinfunction "PA15_38") (pintype "passive"))
    )
    (net (code "44") (name "/TRST") (class "Default")
      (node (ref "J1") (pin "3") (pinfunction "3_3") (pintype "passive"))
      (node (ref "U5") (pin "40") (pinfunction "PB4_40") (pintype "passive"))
    )
    (net (code "45") (name "5V") (class "Default")
      (node (ref "C10") (pin "2") (pinfunction "2_2") (pintype "passive"))
      (node (ref "C9") (pin "1") (pinfunction "1_1") (pintype "passive"))
      (node (ref "F1") (pin "2") (pinfunction "2_2") (pintype "passive"))
      (node (ref "U19") (pin "1") (pinfunction "VIN_1") (pintype "passive"))
      (node (ref "U19") (pin "3") (pinfunction "EN_3") (pintype "passive"))
    )
    (net (code "46") (name "GND") (class "Default")
      (node (ref "C1") (pin "1") (pinfunction "1_1") (pintype "passive"))
      (node (ref "C10") (pin "1") (pinfunction "1_1") (pintype "passive"))
      (node (ref "C11") (pin "2") (pinfunction "2_2") (pintype "passive"))
      (node (ref "C12") (pin "1") (pinfunction "1_1") (pintype "passive"))
      (node (ref "C13") (pin "1") (pinfunction "1_1") (pintype "passive"))
      (node (ref "C14") (pin "1") (pinfunction "1_1") (pintype "passive"))
      (node (ref "C2") (pin "1") (pinfunction "1_1") (pintype "passive"))
      (node (ref "C3") (pin "1") (pinfunction "1_1") (pintype "passive"))
      (node (ref "C4") (pin "1") (pinfunction "1_1") (pintype "passive"))
      (node (ref "C5") (pin "1") (pinfunction "1_1") (pintype "passive"))
      (node (ref "C6") (pin "1") (pinfunction "1_1") (pintype "passive"))
      (node (ref "C7") (pin "1") (pinfunction "1_1") (pintype "passive"))
      (node (ref "C8") (pin "1") (pinfunction "1_1") (pintype "passive"))
      (node (ref "C9") (pin "2") (pinfunction "2_2") (pintype "passive"))
      (node (ref "J1") (pin "10") (pinfunction "10_10") (pintype "passive"))
      (node (ref "J1") (pin "12") (pinfunction "12_12") (pintype "passive"))
      (node (ref "J1") (pin "14") (pinfunction "14_14") (pintype "passive"))
      (node (ref "J1") (pin "16") (pinfunction "16_16") (pintype "passive"))
      (node (ref "J1") (pin "18") (pinfunction "18_18") (pintype "passive"))
      (node (ref "J1") (pin "20") (pinfunction "20_20") (pintype "passive"))
      (node (ref "J1") (pin "4") (pinfunction "4_4") (pintype "passive"))
      (node (ref "J1") (pin "6") (pinfunction "6_6") (pintype "passive"))
      (node (ref "J1") (pin "8") (pinfunction "8_8") (pintype "passive"))
      (node (ref "R1") (pin "2") (pinfunction "2_2") (pintype "passive"))
      (node (ref "R10") (pin "1") (pinfunction "1_1") (pintype "passive"))
      (node (ref "R11") (pin "1") (pinfunction "1_1") (pintype "passive"))
      (node (ref "R12") (pin "2") (pinfunction "2_2") (pintype "passive"))
      (node (ref "R2") (pin "2") (pinfunction "2_2") (pintype "passive"))
      (node (ref "R9") (pin "1") (pinfunction "1_1") (pintype "passive"))
      (node (ref "U1") (pin "A1") (pinfunction "GND_A1") (pintype "passive"))
      (node (ref "U1") (pin "A12") (pinfunction "GND_A12") (pintype "passive"))
      (node (ref "U1") (pin "B1") (pinfunction "GND_B1") (pintype "passive"))
      (node (ref "U1") (pin "B12") (pinfunction "GND_B12") (pintype "passive"))
      (node (ref "U1") (pin "MP1") (pinfunction "SH_MP1") (pintype "passive"))
      (node (ref "U1") (pin "MP2") (pinfunction "SH_MP2") (pintype "passive"))
      (node (ref "U1") (pin "MP3") (pinfunction "SH_MP3") (pintype "passive"))
      (node (ref "U1") (pin "MP4") (pinfunction "SH_MP4") (pintype "passive"))
      (node (ref "U15") (pin "2") (pinfunction "2_2") (pintype "passive"))
      (node (ref "U19") (pin "2") (pinfunction "GND_2") (pintype "passive"))
      (node (ref "U5") (pin "23") (pinfunction "VSS_1_23") (pintype "passive"))
      (node (ref "U5") (pin "35") (pinfunction "VSS_2_35") (pintype "passive"))
      (node (ref "U5") (pin "47") (pinfunction "VSS_3_47") (pintype "passive"))
      (node (ref "U5") (pin "8") (pinfunction "VSSA_8") (pintype "passive"))
    )
    (net (code "47") (name "Net-(D1-Pad2)") (class "Default")
      (node (ref "D1") (pin "2") (pinfunction "2_2") (pintype "passive"))
      (node (ref "U2") (pin "2") (pinfunction "2_2") (pintype "passive"))
    )
    (net (code "48") (name "Net-(D2-Pad2)") (class "Default")
      (node (ref "D2") (pin "2") (pinfunction "2_2") (pintype "passive"))
      (node (ref "U3") (pin "2") (pinfunction "2_2") (pintype "passive"))
    )
    (net (code "49") (name "Net-(D3-Pad2)") (class "Default")
      (node (ref "D3") (pin "2") (pinfunction "2_2") (pintype "passive"))
      (node (ref "U4") (pin "2") (pinfunction "2_2") (pintype "passive"))
    )
    (net (code "50") (name "Net-(D4-Pad2)") (class "Default")
      (node (ref "D4") (pin "2") (pinfunction "2_2") (pintype "passive"))
      (node (ref "U6") (pin "2") (pinfunction "2_2") (pintype "passive"))
    )
    (net (code "51") (name "Net-(D5-Pad2)") (class "Default")
      (node (ref "D5") (pin "2") (pinfunction "2_2") (pintype "passive"))
      (node (ref "U7") (pin "2") (pinfunction "2_2") (pintype "passive"))
    )
    (net (code "52") (name "Net-(D6-Pad2)") (class "Default")
      (node (ref "D6") (pin "2") (pinfunction "2_2") (pintype "passive"))
      (node (ref "U8") (pin "2") (pinfunction "2_2") (pintype "passive"))
    )
    (net (code "53") (name "Net-(D7-Pad2)") (class "Default")
      (node (ref "D7") (pin "2") (pinfunction "2_2") (pintype "passive"))
      (node (ref "U9") (pin "2") (pinfunction "2_2") (pintype "passive"))
    )
    (net (code "54") (name "Net-(D8-Pad2)") (class "Default")
      (node (ref "D8") (pin "2") (pinfunction "2_2") (pintype "passive"))
      (node (ref "U10") (pin "2") (pinfunction "2_2") (pintype "passive"))
    )
    (net (code "55") (name "Net-(D9-Pad2)") (class "Default")
      (node (ref "D9") (pin "2") (pinfunction "2_2") (pintype "passive"))
      (node (ref "U11") (pin "2") (pinfunction "2_2") (pintype "passive"))
    )
    (net (code "56") (name "Net-(D10-Pad2)") (class "Default")
      (node (ref "D10") (pin "2") (pinfunction "2_2") (pintype "passive"))
      (node (ref "U12") (pin "2") (pinfunction "2_2") (pintype "passive"))
    )
    (net (code "57") (name "Net-(D11-Pad2)") (class "Default")
      (node (ref "D11") (pin "2") (pinfunction "2_2") (pintype "passive"))
      (node (ref "U13") (pin "2") (pinfunction "2_2") (pintype "passive"))
    )
    (net (code "58") (name "Net-(D12-Pad2)") (class "Default")
      (node (ref "D12") (pin "2") (pinfunction "2_2") (pintype "passive"))
      (node (ref "U14") (pin "2") (pinfunction "2_2") (pintype "passive"))
    )
    (net (code "59") (name "Net-(D13-Pad2)") (class "Default")
      (node (ref "D13") (pin "2") (pinfunction "2_2") (pintype "passive"))
      (node (ref "U16") (pin "2") (pinfunction "2_2") (pintype "passive"))
    )
    (net (code "60") (name "Net-(D14-Pad2)") (class "Default")
      (node (ref "D14") (pin "2") (pinfunction "2_2") (pintype "passive"))
      (node (ref "U17") (pin "2") (pinfunction "2_2") (pintype "passive"))
    )
    (net (code "61") (name "Net-(D15-Pad2)") (class "Default")
      (node (ref "D15") (pin "2") (pinfunction "2_2") (pintype "passive"))
      (node (ref "U18") (pin "2") (pinfunction "2_2") (pintype "passive"))
    )
    (net (code "62") (name "Net-(J1-Pad1)") (class "Default")
      (node (ref "J1") (pin "1") (pinfunction "1_1") (pintype "passive"))
      (node (ref "J1") (pin "2") (pinfunction "2_2") (pintype "passive"))
      (node (ref "R4") (pin "1") (pinfunction "1_1") (pintype "passive"))
    )
    (net (code "63") (name "Net-(J1-Pad11)") (class "Default")
      (node (ref "J1") (pin "11") (pinfunction "11_11") (pintype "passive"))
      (node (ref "R9") (pin "2") (pinfunction "2_2") (pintype "passive"))
    )
    (net (code "64") (name "Net-(J1-Pad17)") (class "Default")
      (node (ref "J1") (pin "17") (pinfunction "17_17") (pintype "passive"))
      (node (ref "R10") (pin "2") (pinfunction "2_2") (pintype "passive"))
    )
    (net (code "65") (name "Net-(J1-Pad19)") (class "Default")
      (node (ref "J1") (pin "19") (pinfunction "19_19") (pintype "passive"))
      (node (ref "R11") (pin "2") (pinfunction "2_2") (pintype "passive"))
    )
    (net (code "66") (name "Net-(U19-BP)") (class "Default")
      (node (ref "C11") (pin "1") (pinfunction "1_1") (pintype "passive"))
      (node (ref "U19") (pin "4") (pinfunction "BP_4") (pintype "passive"))
    )
    (net (code "67") (name "VBAT") (class "Default")
      (node (ref "C7") (pin "2") (pinfunction "2_2") (pintype "passive"))
      (node (ref "U5") (pin "1") (pinfunction "VBAT_1") (pintype "passive"))
    )
    (net (code "68") (name "VCC3V3") (class "Default")
      (node (ref "C12") (pin "2") (pinfunction "2_2") (pintype "passive"))
      (node (ref "C13") (pin "2") (pinfunction "2_2") (pintype "passive"))
      (node (ref "C3") (pin "2") (pinfunction "2_2") (pintype "passive"))
      (node (ref "C4") (pin "2") (pinfunction "2_2") (pintype "passive"))
      (node (ref "C5") (pin "2") (pinfunction "2_2") (pintype "passive"))
      (node (ref "C6") (pin "2") (pinfunction "2_2") (pintype "passive"))
      (node (ref "R3") (pin "2") (pinfunction "2_2") (pintype "passive"))
      (node (ref "R4") (pin "2") (pinfunction "2_2") (pintype "passive"))
      (node (ref "R5") (pin "2") (pinfunction "2_2") (pintype "passive"))
      (node (ref "R6") (pin "2") (pinfunction "2_2") (pintype "passive"))
      (node (ref "R7") (pin "2") (pinfunction "2_2") (pintype "passive"))
      (node (ref "R8") (pin "2") (pinfunction "2_2") (pintype "passive"))
      (node (ref "U19") (pin "5") (pinfunction "Vout_5") (pintype "passive"))
      (node (ref "U5") (pin "24") (pinfunction "VDD_1_24") (pintype "passive"))
      (node (ref "U5") (pin "36") (pinfunction "VDD_2_36") (pintype "passive"))
      (node (ref "U5") (pin "48") (pinfunction "VDD+3_48") (pintype "passive"))
      (node (ref "U5") (pin "9") (pinfunction "VDDA_9") (pintype "passive"))
    )
    (net (code "69") (name "Vbus") (class "Default")
      (node (ref "C1") (pin "2") (pinfunction "2_2") (pintype "passive"))
      (node (ref "F1") (pin "1") (pinfunction "1_1") (pintype "passive"))
      (node (ref "U1") (pin "A4") (pinfunction "Vbus_A4") (pintype "passive"))
      (node (ref "U1") (pin "A9") (pinfunction "Vbus_A9") (pintype "passive"))
      (node (ref "U1") (pin "B4") (pinfunction "Vbus_B4") (pintype "passive"))
      (node (ref "U1") (pin "B9") (pinfunction "Vbus_B9") (pintype "passive"))
      (node (ref "U15") (pin "5") (pinfunction "5_5") (pintype "passive"))
    )
    (net (code "70") (name "unconnected-(U1-SBU1-PadA8)") (class "Default")
      (node (ref "U1") (pin "A8") (pinfunction "SBU1_A8") (pintype "passive+no_connect"))
    )
    (net (code "71") (name "unconnected-(U1-SBU2-PadB8)") (class "Default")
      (node (ref "U1") (pin "B8") (pinfunction "SBU2_B8") (pintype "passive+no_connect"))
    )
  )
)
